# V01.net
KiCad netlist of a schematic drawn in EAGLE
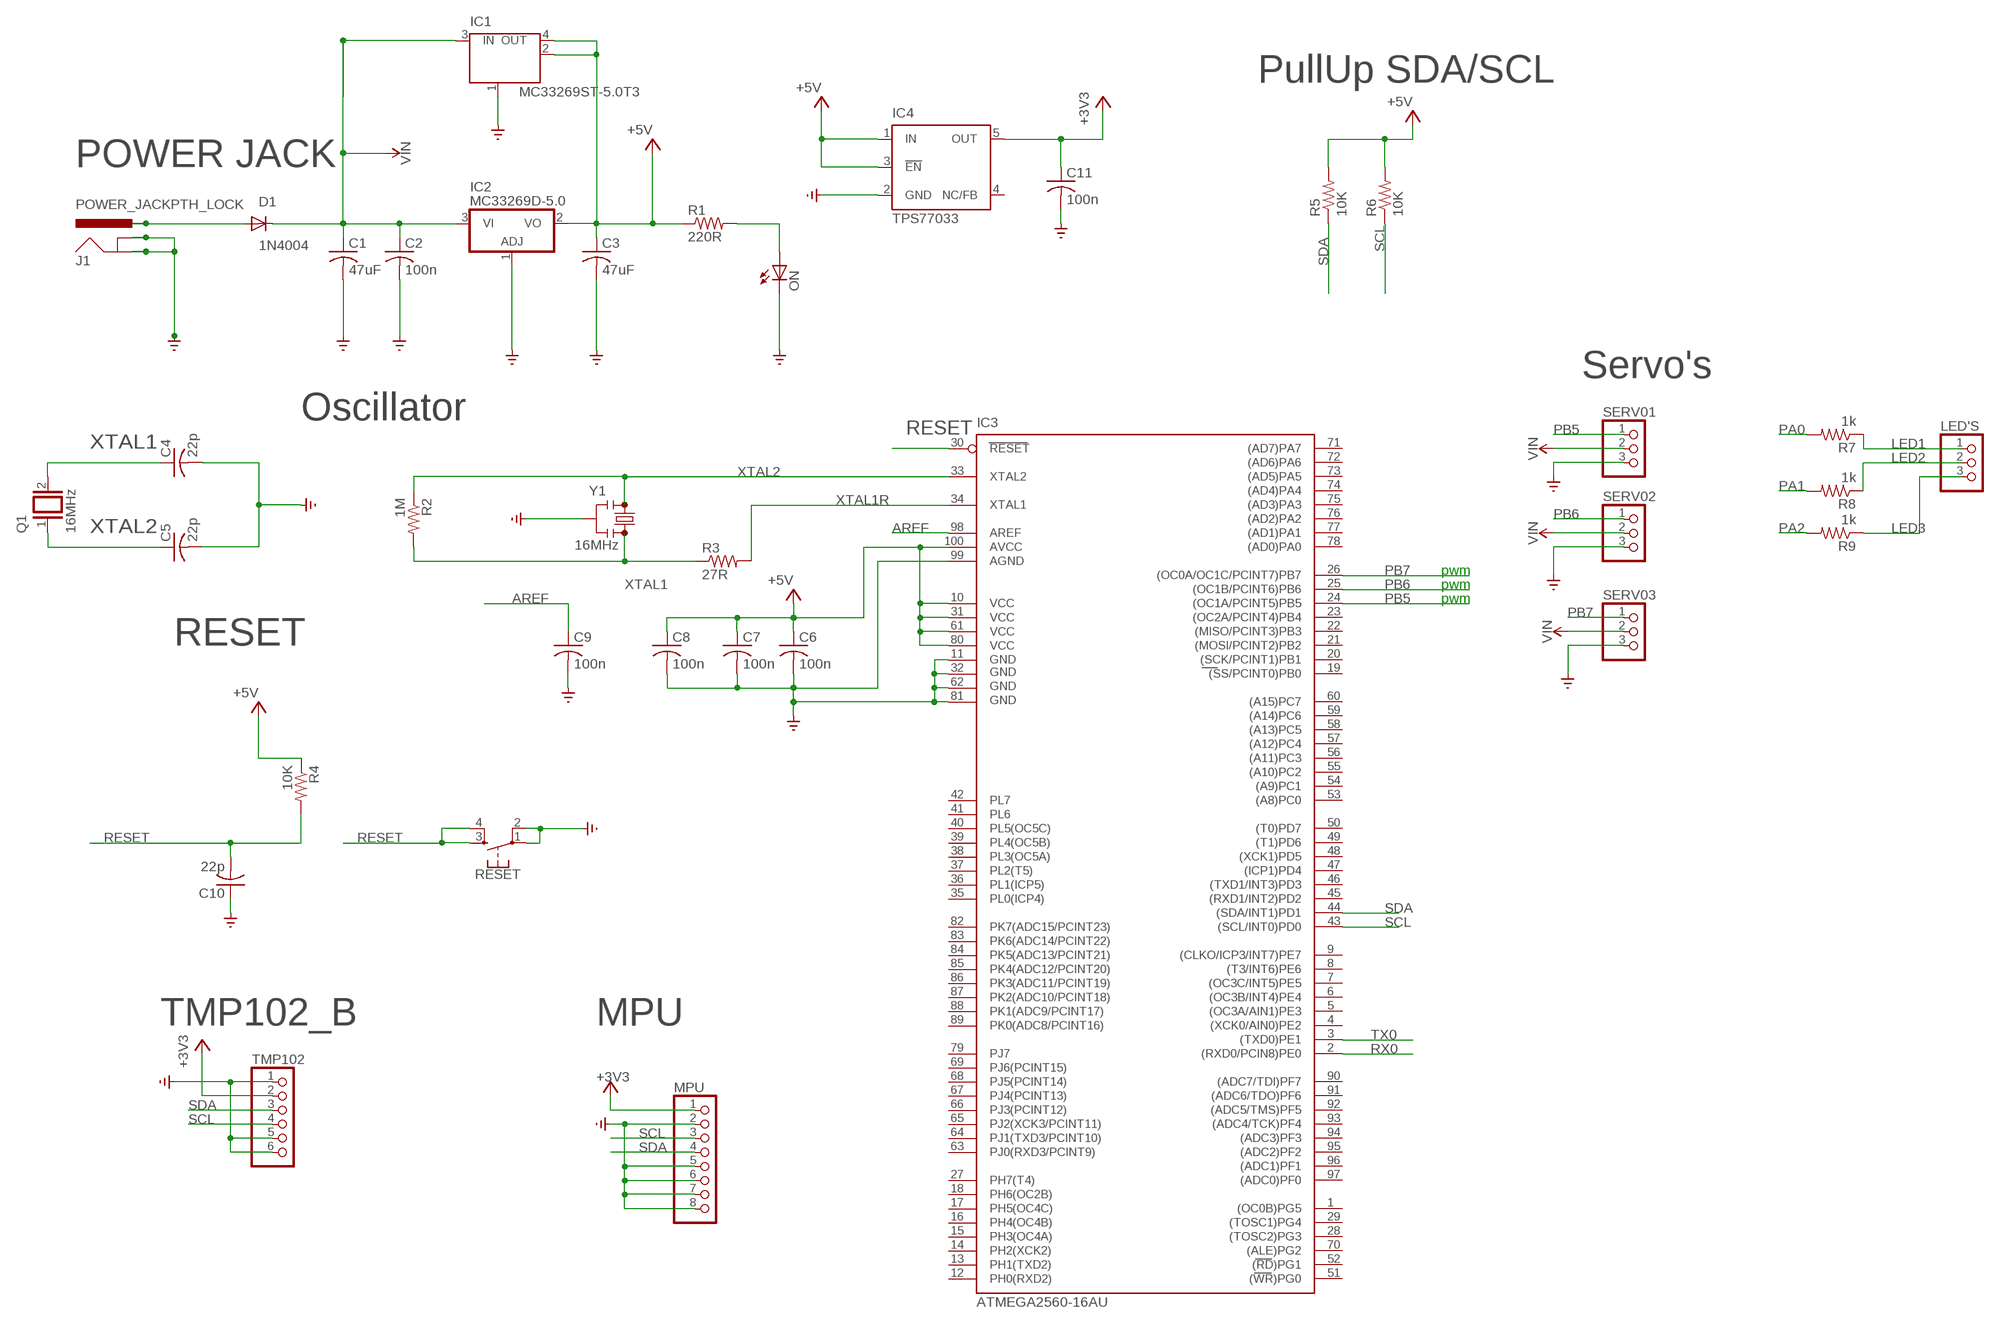
[diagram p0: schematic, sheet 1]

(export (version "E")
  (design (tool "Eeschema 10.0.6"))
  (components
    (comp (ref "C1")
      (value "47uF")
      (footprint "eagle-import:C025-024X044")
      (libsource (lib "eagle-import") (part "C-US025-024X044"))
    )
    (comp (ref "C2")
      (value "100n")
      (footprint "eagle-import:C025-024X044")
      (libsource (lib "eagle-import") (part "C-US025-024X044"))
    )
    (comp (ref "C3")
      (value "47uF")
      (footprint "eagle-import:C025-024X044")
      (libsource (lib "eagle-import") (part "C-US025-024X044"))
    )
    (comp (ref "C4")
      (value "22p")
      (footprint "eagle-import:C025-024X044")
      (libsource (lib "eagle-import") (part "C-US025-024X044"))
    )
    (comp (ref "C5")
      (value "22p")
      (footprint "eagle-import:C025-024X044")
      (libsource (lib "eagle-import") (part "C-US025-024X044"))
    )
    (comp (ref "C6")
      (value "100n")
      (footprint "eagle-import:C025-024X044")
      (libsource (lib "eagle-import") (part "C-US025-024X044"))
    )
    (comp (ref "C7")
      (value "100n")
      (footprint "eagle-import:C025-024X044")
      (libsource (lib "eagle-import") (part "C-US025-024X044"))
    )
    (comp (ref "C8")
      (value "100n")
      (footprint "eagle-import:C025-024X044")
      (libsource (lib "eagle-import") (part "C-US025-024X044"))
    )
    (comp (ref "C9")
      (value "100n")
      (footprint "eagle-import:C025-024X044")
      (libsource (lib "eagle-import") (part "C-US025-024X044"))
    )
    (comp (ref "C10")
      (value "22p")
      (footprint "eagle-import:C025-024X044")
      (libsource (lib "eagle-import") (part "C-US025-024X044"))
    )
    (comp (ref "C11")
      (value "100n")
      (footprint "eagle-import:C025-024X044")
      (libsource (lib "eagle-import") (part "C-US025-024X044"))
    )
    (comp (ref "D1")
      (value "1N4004")
      (footprint "eagle-import:DO41-10")
      (libsource (lib "eagle-import") (part "1N4004"))
    )
    (comp (ref "IC1")
      (value "MC33269ST-5.0T3")
      (footprint "eagle-import:SOT223")
      (libsource (lib "eagle-import") (part "MC33269ST-3.3T3"))
    )
    (comp (ref "IC2")
      (value "MC33269D-5.0")
      (footprint "eagle-import:DPACK")
      (libsource (lib "eagle-import") (part "MC33269?D-5.0"))
    )
    (comp (ref "IC3")
      (value "ATMEGA2560-16AU")
      (footprint "eagle-import:TQFP100")
      (libsource (lib "eagle-import") (part "ATMEGAAU2560-16"))
    )
    (comp (ref "IC4")
      (value "TPS77033")
      (footprint "eagle-import:SOT23-DBV")
      (fields (field (name "MF") "TEXAS INSTRUMENTS") (field (name "MPN") "TPS77033DBVT"))
      (libsource (lib "eagle-import") (part "TPS77033"))
    )
    (comp (ref "J1")
      (value "POWER_JACKPTH_LOCK")
      (footprint "eagle-import:POWER_JACK_PTH_LOCK")
      (libsource (lib "eagle-import") (part "POWER_JACKPTH_LOCK"))
    )
    (comp (ref "LED'S")
      (value "PINHD-1X3")
      (footprint "eagle-import:1X03")
      (libsource (lib "eagle-import") (part "PINHD-1X3"))
    )
    (comp (ref "MPU")
      (value "PINHD-1X8")
      (footprint "eagle-import:1X08")
      (libsource (lib "eagle-import") (part "PINHD-1X8"))
    )
    (comp (ref "ON")
      (value "LED3MM")
      (footprint "eagle-import:LED3MM")
      (libsource (lib "eagle-import") (part "LED3MM"))
    )
    (comp (ref "Q1")
      (value "16MHz")
      (footprint "eagle-import:QS")
      (libsource (lib "eagle-import") (part "XTAL/S"))
    )
    (comp (ref "R1")
      (value "220R")
      (footprint "eagle-import:0204V")
      (libsource (lib "eagle-import") (part "R-US_0204/2V"))
    )
    (comp (ref "R2")
      (value "1M")
      (footprint "eagle-import:0204V")
      (libsource (lib "eagle-import") (part "R-US_0204/2V"))
    )
    (comp (ref "R3")
      (value "27R")
      (footprint "eagle-import:0204V")
      (libsource (lib "eagle-import") (part "R-US_0204/2V"))
    )
    (comp (ref "R4")
      (value "10K")
      (footprint "eagle-import:0204V")
      (libsource (lib "eagle-import") (part "R-US_0204/2V"))
    )
    (comp (ref "R5")
      (value "10K")
      (footprint "eagle-import:0204V")
      (libsource (lib "eagle-import") (part "R-US_0204/2V"))
    )
    (comp (ref "R6")
      (value "10K")
      (footprint "eagle-import:0204V")
      (libsource (lib "eagle-import") (part "R-US_0204/2V"))
    )
    (comp (ref "R7")
      (value "1k")
      (footprint "eagle-import:0204V")
      (libsource (lib "eagle-import") (part "R-US_0204/2V"))
    )
    (comp (ref "R8")
      (value "1k")
      (footprint "eagle-import:0204V")
      (libsource (lib "eagle-import") (part "R-US_0204/2V"))
    )
    (comp (ref "R9")
      (value "1k")
      (footprint "eagle-import:0204V")
      (libsource (lib "eagle-import") (part "R-US_0204/2V"))
    )
    (comp (ref "RESET")
      (value "MOMENTARY-SWITCH-SPST-2-SMD-5.2MM")
      (footprint "eagle-import:TACTILE_SWITCH_SMD_5.2MM")
      (libsource (lib "eagle-import") (part "MOMENTARY-SWITCH-SPST-2-SMD-5.2MM"))
    )
    (comp (ref "SERV01")
      (value "PINHD-1X3")
      (footprint "eagle-import:1X03")
      (libsource (lib "eagle-import") (part "PINHD-1X3"))
    )
    (comp (ref "SERV02")
      (value "PINHD-1X3")
      (footprint "eagle-import:1X03")
      (libsource (lib "eagle-import") (part "PINHD-1X3"))
    )
    (comp (ref "SERV03")
      (value "PINHD-1X3")
      (footprint "eagle-import:1X03")
      (libsource (lib "eagle-import") (part "PINHD-1X3"))
    )
    (comp (ref "TMP102")
      (value "PINHD-1X6")
      (footprint "eagle-import:1X06")
      (libsource (lib "eagle-import") (part "PINHD-1X6"))
    )
    (comp (ref "Y1")
      (value "16MHz")
      (footprint "eagle-import:RESONATOR-SMD-3.2X1.3")
      (libsource (lib "eagle-import") (part "RESONATORSMD-3.2X1.3"))
    )
  )
  (nets
    (net (code "1") (name "+3V3") (class "Default")
      (node (ref "C11") (pin "1") (pinfunction "1_1") (pintype "passive"))
      (node (ref "IC4") (pin "5") (pinfunction "OUT_5") (pintype "passive"))
      (node (ref "MPU") (pin "1") (pinfunction "1_1") (pintype "passive"))
      (node (ref "TMP102") (pin "2") (pinfunction "2_2") (pintype "passive"))
    )
    (net (code "2") (name "+5V") (class "Default")
      (node (ref "C3") (pin "1") (pinfunction "1_1") (pintype "passive"))
      (node (ref "C6") (pin "1") (pinfunction "1_1") (pintype "passive"))
      (node (ref "C7") (pin "1") (pinfunction "1_1") (pintype "passive"))
      (node (ref "C8") (pin "1") (pinfunction "1_1") (pintype "passive"))
      (node (ref "IC1") (pin "2") (pinfunction "OUT_2") (pintype "passive"))
      (node (ref "IC1") (pin "4") (pinfunction "OUT_4") (pintype "passive"))
      (node (ref "IC2") (pin "2") (pinfunction "VO_2") (pintype "passive"))
      (node (ref "IC3") (pin "10") (pinfunction "VCC_10") (pintype "power_in"))
      (node (ref "IC3") (pin "100") (pinfunction "AVCC_100") (pintype "power_in"))
      (node (ref "IC3") (pin "31") (pinfunction "VCC1_31") (pintype "power_in"))
      (node (ref "IC3") (pin "61") (pinfunction "VCC2_61") (pintype "power_in"))
      (node (ref "IC3") (pin "80") (pinfunction "VCC3_80") (pintype "power_in"))
      (node (ref "IC4") (pin "1") (pinfunction "IN_1") (pintype "input"))
      (node (ref "IC4") (pin "3") (pinfunction "~{EN}_3") (pintype "input"))
      (node (ref "R1") (pin "1") (pinfunction "1_1") (pintype "passive"))
      (node (ref "R4") (pin "1") (pinfunction "1_1") (pintype "passive"))
      (node (ref "R5") (pin "2") (pinfunction "2_2") (pintype "passive"))
      (node (ref "R6") (pin "2") (pinfunction "2_2") (pintype "passive"))
    )
    (net (code "3") (name "/AREF") (class "Default")
      (node (ref "C9") (pin "1") (pinfunction "1_1") (pintype "passive"))
      (node (ref "IC3") (pin "98") (pinfunction "AREF_98") (pintype "bidirectional"))
    )
    (net (code "4") (name "/LED1") (class "Default")
      (node (ref "LED'S") (pin "1") (pinfunction "1_1") (pintype "passive"))
      (node (ref "R7") (pin "1") (pinfunction "1_1") (pintype "passive"))
    )
    (net (code "5") (name "/LED2") (class "Default")
      (node (ref "LED'S") (pin "2") (pinfunction "2_2") (pintype "passive"))
      (node (ref "R8") (pin "1") (pinfunction "1_1") (pintype "passive"))
    )
    (net (code "6") (name "/LED3") (class "Default")
      (node (ref "LED'S") (pin "3") (pinfunction "3_3") (pintype "passive"))
      (node (ref "R9") (pin "1") (pinfunction "1_1") (pintype "passive"))
    )
    (net (code "7") (name "/PA0") (class "Default")
      (node (ref "R7") (pin "2") (pinfunction "2_2") (pintype "passive"))
    )
    (net (code "8") (name "/PA1") (class "Default")
      (node (ref "R8") (pin "2") (pinfunction "2_2") (pintype "passive"))
    )
    (net (code "9") (name "/PA2") (class "Default")
      (node (ref "R9") (pin "2") (pinfunction "2_2") (pintype "passive"))
    )
    (net (code "10") (name "/PB5") (class "Default")
      (node (ref "IC3") (pin "24") (pinfunction "(OC1A/PCINT5)PB5_24") (pintype "bidirectional"))
      (node (ref "SERV01") (pin "1") (pinfunction "1_1") (pintype "passive"))
    )
    (net (code "11") (name "/PB6") (class "Default")
      (node (ref "IC3") (pin "25") (pinfunction "(OC1B/PCINT6)PB6_25") (pintype "bidirectional"))
      (node (ref "SERV02") (pin "1") (pinfunction "1_1") (pintype "passive"))
    )
    (net (code "12") (name "/PB7") (class "Default")
      (node (ref "IC3") (pin "26") (pinfunction "(OC0A/OC1C/PCINT7)PB7_26") (pintype "bidirectional"))
      (node (ref "SERV03") (pin "1") (pinfunction "1_1") (pintype "passive"))
    )
    (net (code "13") (name "/RESET") (class "Default")
      (node (ref "C10") (pin "2") (pinfunction "2_2") (pintype "passive"))
      (node (ref "IC3") (pin "30") (pinfunction "RESET_30") (pintype "input"))
      (node (ref "R4") (pin "2") (pinfunction "2_2") (pintype "passive"))
      (node (ref "RESET") (pin "3") (pinfunction "3_3") (pintype "passive"))
      (node (ref "RESET") (pin "4") (pinfunction "4_4") (pintype "passive"))
    )
    (net (code "14") (name "/RX0") (class "Default")
      (node (ref "IC3") (pin "2") (pinfunction "(RXD0/PCIN8)PE0_2") (pintype "bidirectional"))
    )
    (net (code "15") (name "/SCL") (class "Default")
      (node (ref "IC3") (pin "43") (pinfunction "(SCL/INT0)PD0_43") (pintype "bidirectional"))
      (node (ref "MPU") (pin "3") (pinfunction "3_3") (pintype "passive"))
      (node (ref "R6") (pin "1") (pinfunction "1_1") (pintype "passive"))
      (node (ref "TMP102") (pin "4") (pinfunction "4_4") (pintype "passive"))
    )
    (net (code "16") (name "/SDA") (class "Default")
      (node (ref "IC3") (pin "44") (pinfunction "(SDA/INT1)PD1_44") (pintype "bidirectional"))
      (node (ref "MPU") (pin "4") (pinfunction "4_4") (pintype "passive"))
      (node (ref "R5") (pin "1") (pinfunction "1_1") (pintype "passive"))
      (node (ref "TMP102") (pin "3") (pinfunction "3_3") (pintype "passive"))
    )
    (net (code "17") (name "/TX0") (class "Default")
      (node (ref "IC3") (pin "3") (pinfunction "(TXD0)PE1_3") (pintype "bidirectional"))
    )
    (net (code "18") (name "/XTAL1") (class "Default")
      (node (ref "C4") (pin "1") (pinfunction "1_1") (pintype "passive"))
      (node (ref "Q1") (pin "2") (pinfunction "2_2") (pintype "passive"))
      (node (ref "R2") (pin "2") (pinfunction "2_2") (pintype "passive"))
      (node (ref "R3") (pin "1") (pinfunction "1_1") (pintype "passive"))
      (node (ref "Y1") (pin "3") (pinfunction "3_3") (pintype "passive"))
    )
    (net (code "19") (name "/XTAL1R") (class "Default")
      (node (ref "IC3") (pin "34") (pinfunction "XTAL1_34") (pintype "input"))
      (node (ref "R3") (pin "2") (pinfunction "2_2") (pintype "passive"))
    )
    (net (code "20") (name "/XTAL2") (class "Default")
      (node (ref "C5") (pin "1") (pinfunction "1_1") (pintype "passive"))
      (node (ref "IC3") (pin "33") (pinfunction "XTAL2_33") (pintype "output"))
      (node (ref "Q1") (pin "1") (pinfunction "1_1") (pintype "passive"))
      (node (ref "R2") (pin "1") (pinfunction "1_1") (pintype "passive"))
      (node (ref "Y1") (pin "1") (pinfunction "1_1") (pintype "passive"))
    )
    (net (code "21") (name "GND_") (class "Default")
      (node (ref "C1") (pin "2") (pinfunction "2_2") (pintype "passive"))
      (node (ref "C10") (pin "1") (pinfunction "1_1") (pintype "passive"))
      (node (ref "C11") (pin "2") (pinfunction "2_2") (pintype "passive"))
      (node (ref "C2") (pin "2") (pinfunction "2_2") (pintype "passive"))
      (node (ref "C3") (pin "2") (pinfunction "2_2") (pintype "passive"))
      (node (ref "C4") (pin "2") (pinfunction "2_2") (pintype "passive"))
      (node (ref "C5") (pin "2") (pinfunction "2_2") (pintype "passive"))
      (node (ref "C6") (pin "2") (pinfunction "2_2") (pintype "passive"))
      (node (ref "C7") (pin "2") (pinfunction "2_2") (pintype "passive"))
      (node (ref "C8") (pin "2") (pinfunction "2_2") (pintype "passive"))
      (node (ref "C9") (pin "2") (pinfunction "2_2") (pintype "passive"))
      (node (ref "IC1") (pin "1") (pinfunction "GND/ADJ_1") (pintype "input"))
      (node (ref "IC2") (pin "1") (pinfunction "ADJ_1") (pintype "input"))
      (node (ref "IC3") (pin "11") (pinfunction "GND_11") (pintype "power_in"))
      (node (ref "IC3") (pin "32") (pinfunction "GND1_32") (pintype "power_in"))
      (node (ref "IC3") (pin "62") (pinfunction "GND2_62") (pintype "power_in"))
      (node (ref "IC3") (pin "81") (pinfunction "GND3_81") (pintype "power_in"))
      (node (ref "IC3") (pin "99") (pinfunction "AGND_99") (pintype "power_in"))
      (node (ref "IC4") (pin "2") (pinfunction "GND_2") (pintype "power_in"))
      (node (ref "J1") (pin "GND") (pinfunction "GND_GND") (pintype "bidirectional"))
      (node (ref "J1") (pin "GNDBREAK") (pinfunction "GNDBREAK_GNDBREAK") (pintype "bidirectional"))
      (node (ref "MPU") (pin "2") (pinfunction "2_2") (pintype "passive"))
      (node (ref "MPU") (pin "5") (pinfunction "5_5") (pintype "passive"))
      (node (ref "MPU") (pin "6") (pinfunction "6_6") (pintype "passive"))
      (node (ref "MPU") (pin "7") (pinfunction "7_7") (pintype "passive"))
      (node (ref "MPU") (pin "8") (pinfunction "8_8") (pintype "passive"))
      (node (ref "ON") (pin "K") (pinfunction "C_K") (pintype "passive"))
      (node (ref "RESET") (pin "1") (pinfunction "1_1") (pintype "passive"))
      (node (ref "RESET") (pin "2") (pinfunction "2_2") (pintype "passive"))
      (node (ref "SERV01") (pin "3") (pinfunction "3_3") (pintype "passive"))
      (node (ref "SERV02") (pin "3") (pinfunction "3_3") (pintype "passive"))
      (node (ref "SERV03") (pin "3") (pinfunction "3_3") (pintype "passive"))
      (node (ref "TMP102") (pin "1") (pinfunction "1_1") (pintype "passive"))
      (node (ref "TMP102") (pin "5") (pinfunction "5_5") (pintype "passive"))
      (node (ref "TMP102") (pin "6") (pinfunction "6_6") (pintype "passive"))
      (node (ref "Y1") (pin "2") (pinfunction "2_2") (pintype "passive"))
    )
    (net (code "22") (name "Net-(D1-PadA)") (class "Default")
      (node (ref "D1") (pin "A") (pinfunction "A_A") (pintype "passive"))
      (node (ref "J1") (pin "PWR") (pinfunction "PWR_PWR") (pintype "bidirectional"))
    )
    (net (code "23") (name "Net-(ON-PadA)") (class "Default")
      (node (ref "ON") (pin "A") (pinfunction "A_A") (pintype "passive"))
      (node (ref "R1") (pin "2") (pinfunction "2_2") (pintype "passive"))
    )
    (net (code "24") (name "VIN") (class "Default")
      (node (ref "C1") (pin "1") (pinfunction "1_1") (pintype "passive"))
      (node (ref "C2") (pin "1") (pinfunction "1_1") (pintype "passive"))
      (node (ref "D1") (pin "C") (pinfunction "C_C") (pintype "passive"))
      (node (ref "IC1") (pin "3") (pinfunction "IN_3") (pintype "input"))
      (node (ref "IC2") (pin "3") (pinfunction "VI_3") (pintype "input"))
      (node (ref "SERV01") (pin "2") (pinfunction "2_2") (pintype "passive"))
      (node (ref "SERV02") (pin "2") (pinfunction "2_2") (pintype "passive"))
      (node (ref "SERV03") (pin "2") (pinfunction "2_2") (pintype "passive"))
    )
    (net (code "25") (name "unconnected-(IC3-(A8)PC0-Pad53)") (class "Default")
      (node (ref "IC3") (pin "53") (pinfunction "(A8)PC0_53") (pintype "bidirectional"))
    )
    (net (code "26") (name "unconnected-(IC3-(A9)PC1-Pad54)") (class "Default")
      (node (ref "IC3") (pin "54") (pinfunction "(A9)PC1_54") (pintype "bidirectional"))
    )
    (net (code "27") (name "unconnected-(IC3-(A10)PC2-Pad55)") (class "Default")
      (node (ref "IC3") (pin "55") (pinfunction "(A10)PC2_55") (pintype "bidirectional"))
    )
    (net (code "28") (name "unconnected-(IC3-(A11)PC3-Pad56)") (class "Default")
      (node (ref "IC3") (pin "56") (pinfunction "(A11)PC3_56") (pintype "bidirectional"))
    )
    (net (code "29") (name "unconnected-(IC3-(A12)PC4-Pad57)") (class "Default")
      (node (ref "IC3") (pin "57") (pinfunction "(A12)PC4_57") (pintype "bidirectional"))
    )
    (net (code "30") (name "unconnected-(IC3-(A13)PC5-Pad58)") (class "Default")
      (node (ref "IC3") (pin "58") (pinfunction "(A13)PC5_58") (pintype "bidirectional"))
    )
    (net (code "31") (name "unconnected-(IC3-(A14)PC6-Pad59)") (class "Default")
      (node (ref "IC3") (pin "59") (pinfunction "(A14)PC6_59") (pintype "bidirectional"))
    )
    (net (code "32") (name "unconnected-(IC3-(A15)PC7-Pad60)") (class "Default")
      (node (ref "IC3") (pin "60") (pinfunction "(A15)PC7_60") (pintype "bidirectional"))
    )
    (net (code "33") (name "unconnected-(IC3-(AD0)PA0-Pad78)") (class "Default")
      (node (ref "IC3") (pin "78") (pinfunction "(AD0)PA0_78") (pintype "bidirectional"))
    )
    (net (code "34") (name "unconnected-(IC3-(AD1)PA1-Pad77)") (class "Default")
      (node (ref "IC3") (pin "77") (pinfunction "(AD1)PA1_77") (pintype "bidirectional"))
    )
    (net (code "35") (name "unconnected-(IC3-(AD2)PA2-Pad76)") (class "Default")
      (node (ref "IC3") (pin "76") (pinfunction "(AD2)PA2_76") (pintype "bidirectional"))
    )
    (net (code "36") (name "unconnected-(IC3-(AD3)PA3-Pad75)") (class "Default")
      (node (ref "IC3") (pin "75") (pinfunction "(AD3)PA3_75") (pintype "bidirectional"))
    )
    (net (code "37") (name "unconnected-(IC3-(AD4)PA4-Pad74)") (class "Default")
      (node (ref "IC3") (pin "74") (pinfunction "(AD4)PA4_74") (pintype "bidirectional"))
    )
    (net (code "38") (name "unconnected-(IC3-(AD5)PA5-Pad73)") (class "Default")
      (node (ref "IC3") (pin "73") (pinfunction "(AD5)PA5_73") (pintype "bidirectional"))
    )
    (net (code "39") (name "unconnected-(IC3-(AD6)PA6-Pad72)") (class "Default")
      (node (ref "IC3") (pin "72") (pinfunction "(AD6)PA6_72") (pintype "bidirectional"))
    )
    (net (code "40") (name "unconnected-(IC3-(AD7)PA7-Pad71)") (class "Default")
      (node (ref "IC3") (pin "71") (pinfunction "(AD7)PA7_71") (pintype "bidirectional"))
    )
    (net (code "41") (name "unconnected-(IC3-(ADC0)PF0-Pad97)") (class "Default")
      (node (ref "IC3") (pin "97") (pinfunction "(ADC0)PF0_97") (pintype "bidirectional"))
    )
    (net (code "42") (name "unconnected-(IC3-(ADC1)PF1-Pad96)") (class "Default")
      (node (ref "IC3") (pin "96") (pinfunction "(ADC1)PF1_96") (pintype "bidirectional"))
    )
    (net (code "43") (name "unconnected-(IC3-(ADC2)PF2-Pad95)") (class "Default")
      (node (ref "IC3") (pin "95") (pinfunction "(ADC2)PF2_95") (pintype "bidirectional"))
    )
    (net (code "44") (name "unconnected-(IC3-(ADC3)PF3-Pad94)") (class "Default")
      (node (ref "IC3") (pin "94") (pinfunction "(ADC3)PF3_94") (pintype "bidirectional"))
    )
    (net (code "45") (name "unconnected-(IC3-(ADC4{slash}TCK)PF4-Pad93)") (class "Default")
      (node (ref "IC3") (pin "93") (pinfunction "(ADC4/TCK)PF4_93") (pintype "bidirectional"))
    )
    (net (code "46") (name "unconnected-(IC3-(ADC5{slash}TMS)PF5-Pad92)") (class "Default")
      (node (ref "IC3") (pin "92") (pinfunction "(ADC5/TMS)PF5_92") (pintype "bidirectional"))
    )
    (net (code "47") (name "unconnected-(IC3-(ADC6{slash}TDO)PF6-Pad91)") (class "Default")
      (node (ref "IC3") (pin "91") (pinfunction "(ADC6/TDO)PF6_91") (pintype "bidirectional"))
    )
    (net (code "48") (name "unconnected-(IC3-(ADC7{slash}TDI)PF7-Pad90)") (class "Default")
      (node (ref "IC3") (pin "90") (pinfunction "(ADC7/TDI)PF7_90") (pintype "bidirectional"))
    )
    (net (code "49") (name "unconnected-(IC3-(ALE)PG2-Pad70)") (class "Default")
      (node (ref "IC3") (pin "70") (pinfunction "(ALE)PG2_70") (pintype "bidirectional"))
    )
    (net (code "50") (name "unconnected-(IC3-(CLKO{slash}ICP3{slash}INT7)PE7-Pad9)") (class "Default")
      (node (ref "IC3") (pin "9") (pinfunction "(CLKO/ICP3/INT7)PE7_9") (pintype "bidirectional"))
    )
    (net (code "51") (name "unconnected-(IC3-(ICP1)PD4-Pad47)") (class "Default")
      (node (ref "IC3") (pin "47") (pinfunction "(ICP1)PD4_47") (pintype "bidirectional"))
    )
    (net (code "52") (name "unconnected-(IC3-(MISO{slash}PCINT3)PB3-Pad22)") (class "Default")
      (node (ref "IC3") (pin "22") (pinfunction "(MISO/PCINT3)PB3_22") (pintype "bidirectional"))
    )
    (net (code "53") (name "unconnected-(IC3-(MOSI{slash}PCINT2)PB2-Pad21)") (class "Default")
      (node (ref "IC3") (pin "21") (pinfunction "(MOSI/PCINT2)PB2_21") (pintype "bidirectional"))
    )
    (net (code "54") (name "unconnected-(IC3-(OC0B)PG5-Pad1)") (class "Default")
      (node (ref "IC3") (pin "1") (pinfunction "(OC0B)PG5_1") (pintype "bidirectional"))
    )
    (net (code "55") (name "unconnected-(IC3-(OC2A{slash}PCINT4)PB4-Pad23)") (class "Default")
      (node (ref "IC3") (pin "23") (pinfunction "(OC2A/PCINT4)PB4_23") (pintype "bidirectional"))
    )
    (net (code "56") (name "unconnected-(IC3-(OC3A{slash}AIN1)PE3-Pad5)") (class "Default")
      (node (ref "IC3") (pin "5") (pinfunction "(OC3A/AIN1)PE3_5") (pintype "bidirectional"))
    )
    (net (code "57") (name "unconnected-(IC3-(OC3B{slash}INT4)PE4-Pad6)") (class "Default")
      (node (ref "IC3") (pin "6") (pinfunction "(OC3B/INT4)PE4_6") (pintype "bidirectional"))
    )
    (net (code "58") (name "unconnected-(IC3-(OC3C{slash}INT5)PE5-Pad7)") (class "Default")
      (node (ref "IC3") (pin "7") (pinfunction "(OC3C/INT5)PE5_7") (pintype "bidirectional"))
    )
    (net (code "59") (name "unconnected-(IC3-(RD)PG1-Pad52)") (class "Default")
      (node (ref "IC3") (pin "52") (pinfunction "(RD)PG1_52") (pintype "bidirectional"))
    )
    (net (code "60") (name "unconnected-(IC3-(RXD1{slash}INT2)PD2-Pad45)") (class "Default")
      (node (ref "IC3") (pin "45") (pinfunction "(RXD1/INT2)PD2_45") (pintype "bidirectional"))
    )
    (net (code "61") (name "unconnected-(IC3-(SCK{slash}PCINT1)PB1-Pad20)") (class "Default")
      (node (ref "IC3") (pin "20") (pinfunction "(SCK/PCINT1)PB1_20") (pintype "bidirectional"))
    )
    (net (code "62") (name "unconnected-(IC3-(SS{slash}PCINT0)PB0-Pad19)") (class "Default")
      (node (ref "IC3") (pin "19") (pinfunction "(SS/PCINT0)PB0_19") (pintype "bidirectional"))
    )
    (net (code "63") (name "unconnected-(IC3-(T0)PD7-Pad50)") (class "Default")
      (node (ref "IC3") (pin "50") (pinfunction "(T0)PD7_50") (pintype "bidirectional"))
    )
    (net (code "64") (name "unconnected-(IC3-(T1)PD6-Pad49)") (class "Default")
      (node (ref "IC3") (pin "49") (pinfunction "(T1)PD6_49") (pintype "bidirectional"))
    )
    (net (code "65") (name "unconnected-(IC3-(T3{slash}INT6)PE6-Pad8)") (class "Default")
      (node (ref "IC3") (pin "8") (pinfunction "(T3/INT6)PE6_8") (pintype "bidirectional"))
    )
    (net (code "66") (name "unconnected-(IC3-(TOSC1)PG4-Pad29)") (class "Default")
      (node (ref "IC3") (pin "29") (pinfunction "(TOSC1)PG4_29") (pintype "bidirectional"))
    )
    (net (code "67") (name "unconnected-(IC3-(TOSC2)PG3-Pad28)") (class "Default")
      (node (ref "IC3") (pin "28") (pinfunction "(TOSC2)PG3_28") (pintype "bidirectional"))
    )
    (net (code "68") (name "unconnected-(IC3-(TXD1{slash}INT3)PD3-Pad46)") (class "Default")
      (node (ref "IC3") (pin "46") (pinfunction "(TXD1/INT3)PD3_46") (pintype "bidirectional"))
    )
    (net (code "69") (name "unconnected-(IC3-(WR)PG0-Pad51)") (class "Default")
      (node (ref "IC3") (pin "51") (pinfunction "(WR)PG0_51") (pintype "bidirectional"))
    )
    (net (code "70") (name "unconnected-(IC3-(XCK0{slash}AIN0)PE2-Pad4)") (class "Default")
      (node (ref "IC3") (pin "4") (pinfunction "(XCK0/AIN0)PE2_4") (pintype "bidirectional"))
    )
    (net (code "71") (name "unconnected-(IC3-(XCK1)PD5-Pad48)") (class "Default")
      (node (ref "IC3") (pin "48") (pinfunction "(XCK1)PD5_48") (pintype "bidirectional"))
    )
    (net (code "72") (name "unconnected-(IC3-PH0(RXD2)-Pad12)") (class "Default")
      (node (ref "IC3") (pin "12") (pinfunction "PH0(RXD2)_12") (pintype "bidirectional"))
    )
    (net (code "73") (name "unconnected-(IC3-PH1(TXD2)-Pad13)") (class "Default")
      (node (ref "IC3") (pin "13") (pinfunction "PH1(TXD2)_13") (pintype "bidirectional"))
    )
    (net (code "74") (name "unconnected-(IC3-PH2(XCK2)-Pad14)") (class "Default")
      (node (ref "IC3") (pin "14") (pinfunction "PH2(XCK2)_14") (pintype "bidirectional"))
    )
    (net (code "75") (name "unconnected-(IC3-PH3(OC4A)-Pad15)") (class "Default")
      (node (ref "IC3") (pin "15") (pinfunction "PH3(OC4A)_15") (pintype "bidirectional"))
    )
    (net (code "76") (name "unconnected-(IC3-PH4(OC4B)-Pad16)") (class "Default")
      (node (ref "IC3") (pin "16") (pinfunction "PH4(OC4B)_16") (pintype "bidirectional"))
    )
    (net (code "77") (name "unconnected-(IC3-PH5(OC4C)-Pad17)") (class "Default")
      (node (ref "IC3") (pin "17") (pinfunction "PH5(OC4C)_17") (pintype "bidirectional"))
    )
    (net (code "78") (name "unconnected-(IC3-PH6(OC2B)-Pad18)") (class "Default")
      (node (ref "IC3") (pin "18") (pinfunction "PH6(OC2B)_18") (pintype "bidirectional"))
    )
    (net (code "79") (name "unconnected-(IC3-PH7(T4)-Pad27)") (class "Default")
      (node (ref "IC3") (pin "27") (pinfunction "PH7(T4)_27") (pintype "bidirectional"))
    )
    (net (code "80") (name "unconnected-(IC3-PJ0(RXD3{slash}PCINT9)-Pad63)") (class "Default")
      (node (ref "IC3") (pin "63") (pinfunction "PJ0(RXD3/PCINT9)_63") (pintype "bidirectional"))
    )
    (net (code "81") (name "unconnected-(IC3-PJ1(TXD3{slash}PCINT10)-Pad64)") (class "Default")
      (node (ref "IC3") (pin "64") (pinfunction "PJ1(TXD3/PCINT10)_64") (pintype "bidirectional"))
    )
    (net (code "82") (name "unconnected-(IC3-PJ2(XCK3{slash}PCINT11)-Pad65)") (class "Default")
      (node (ref "IC3") (pin "65") (pinfunction "PJ2(XCK3/PCINT11)_65") (pintype "bidirectional"))
    )
    (net (code "83") (name "unconnected-(IC3-PJ3(PCINT12)-Pad66)") (class "Default")
      (node (ref "IC3") (pin "66") (pinfunction "PJ3(PCINT12)_66") (pintype "bidirectional"))
    )
    (net (code "84") (name "unconnected-(IC3-PJ4(PCINT13)-Pad67)") (class "Default")
      (node (ref "IC3") (pin "67") (pinfunction "PJ4(PCINT13)_67") (pintype "bidirectional"))
    )
    (net (code "85") (name "unconnected-(IC3-PJ5(PCINT14)-Pad68)") (class "Default")
      (node (ref "IC3") (pin "68") (pinfunction "PJ5(PCINT14)_68") (pintype "bidirectional"))
    )
    (net (code "86") (name "unconnected-(IC3-PJ6(PCINT15)-Pad69)") (class "Default")
      (node (ref "IC3") (pin "69") (pinfunction "PJ6(PCINT15)_69") (pintype "bidirectional"))
    )
    (net (code "87") (name "unconnected-(IC3-PJ7-Pad79)") (class "Default")
      (node (ref "IC3") (pin "79") (pinfunction "PJ7_79") (pintype "bidirectional"))
    )
    (net (code "88") (name "unconnected-(IC3-PK0(ADC8{slash}PCINT16)-Pad89)") (class "Default")
      (node (ref "IC3") (pin "89") (pinfunction "PK0(ADC8/PCINT16)_89") (pintype "bidirectional"))
    )
    (net (code "89") (name "unconnected-(IC3-PK1(ADC9{slash}PCINT17)-Pad88)") (class "Default")
      (node (ref "IC3") (pin "88") (pinfunction "PK1(ADC9/PCINT17)_88") (pintype "bidirectional"))
    )
    (net (code "90") (name "unconnected-(IC3-PK2(ADC10{slash}PCINT18)-Pad87)") (class "Default")
      (node (ref "IC3") (pin "87") (pinfunction "PK2(ADC10/PCINT18)_87") (pintype "bidirectional"))
    )
    (net (code "91") (name "unconnected-(IC3-PK3(ADC11{slash}PCINT19)-Pad86)") (class "Default")
      (node (ref "IC3") (pin "86") (pinfunction "PK3(ADC11/PCINT19)_86") (pintype "bidirectional"))
    )
    (net (code "92") (name "unconnected-(IC3-PK4(ADC12{slash}PCINT20)-Pad85)") (class "Default")
      (node (ref "IC3") (pin "85") (pinfunction "PK4(ADC12/PCINT20)_85") (pintype "bidirectional"))
    )
    (net (code "93") (name "unconnected-(IC3-PK5(ADC13{slash}PCINT21)-Pad84)") (class "Default")
      (node (ref "IC3") (pin "84") (pinfunction "PK5(ADC13/PCINT21)_84") (pintype "bidirectional"))
    )
    (net (code "94") (name "unconnected-(IC3-PK6(ADC14{slash}PCINT22)-Pad83)") (class "Default")
      (node (ref "IC3") (pin "83") (pinfunction "PK6(ADC14/PCINT22)_83") (pintype "bidirectional"))
    )
    (net (code "95") (name "unconnected-(IC3-PK7(ADC15{slash}PCINT23)-Pad82)") (class "Default")
      (node (ref "IC3") (pin "82") (pinfunction "PK7(ADC15/PCINT23)_82") (pintype "bidirectional"))
    )
    (net (code "96") (name "unconnected-(IC3-PL0(ICP4)-Pad35)") (class "Default")
      (node (ref "IC3") (pin "35") (pinfunction "PL0(ICP4)_35") (pintype "bidirectional"))
    )
    (net (code "97") (name "unconnected-(IC3-PL1(ICP5)-Pad36)") (class "Default")
      (node (ref "IC3") (pin "36") (pinfunction "PL1(ICP5)_36") (pintype "bidirectional"))
    )
    (net (code "98") (name "unconnected-(IC3-PL2(T5)-Pad37)") (class "Default")
      (node (ref "IC3") (pin "37") (pinfunction "PL2(T5)_37") (pintype "bidirectional"))
    )
    (net (code "99") (name "unconnected-(IC3-PL3(OC5A)-Pad38)") (class "Default")
      (node (ref "IC3") (pin "38") (pinfunction "PL3(OC5A)_38") (pintype "bidirectional"))
    )
    (net (code "100") (name "unconnected-(IC3-PL4(OC5B)-Pad39)") (class "Default")
      (node (ref "IC3") (pin "39") (pinfunction "PL4(OC5B)_39") (pintype "bidirectional"))
    )
    (net (code "101") (name "unconnected-(IC3-PL5(OC5C)-Pad40)") (class "Default")
      (node (ref "IC3") (pin "40") (pinfunction "PL5(OC5C)_40") (pintype "bidirectional"))
    )
    (net (code "102") (name "unconnected-(IC3-PL6-Pad41)") (class "Default")
      (node (ref "IC3") (pin "41") (pinfunction "PL6_41") (pintype "bidirectional"))
    )
    (net (code "103") (name "unconnected-(IC3-PL7-Pad42)") (class "Default")
      (node (ref "IC3") (pin "42") (pinfunction "PL7_42") (pintype "bidirectional"))
    )
    (net (code "104") (name "unconnected-(IC4-NC{slash}FB-Pad4)") (class "Default")
      (node (ref "IC4") (pin "4") (pinfunction "NC/FB_4") (pintype "passive"))
    )
  )
)
